# Adafruit_PN532_Breakout_v1_6.net
KiCad netlist of a schematic drawn in EAGLE
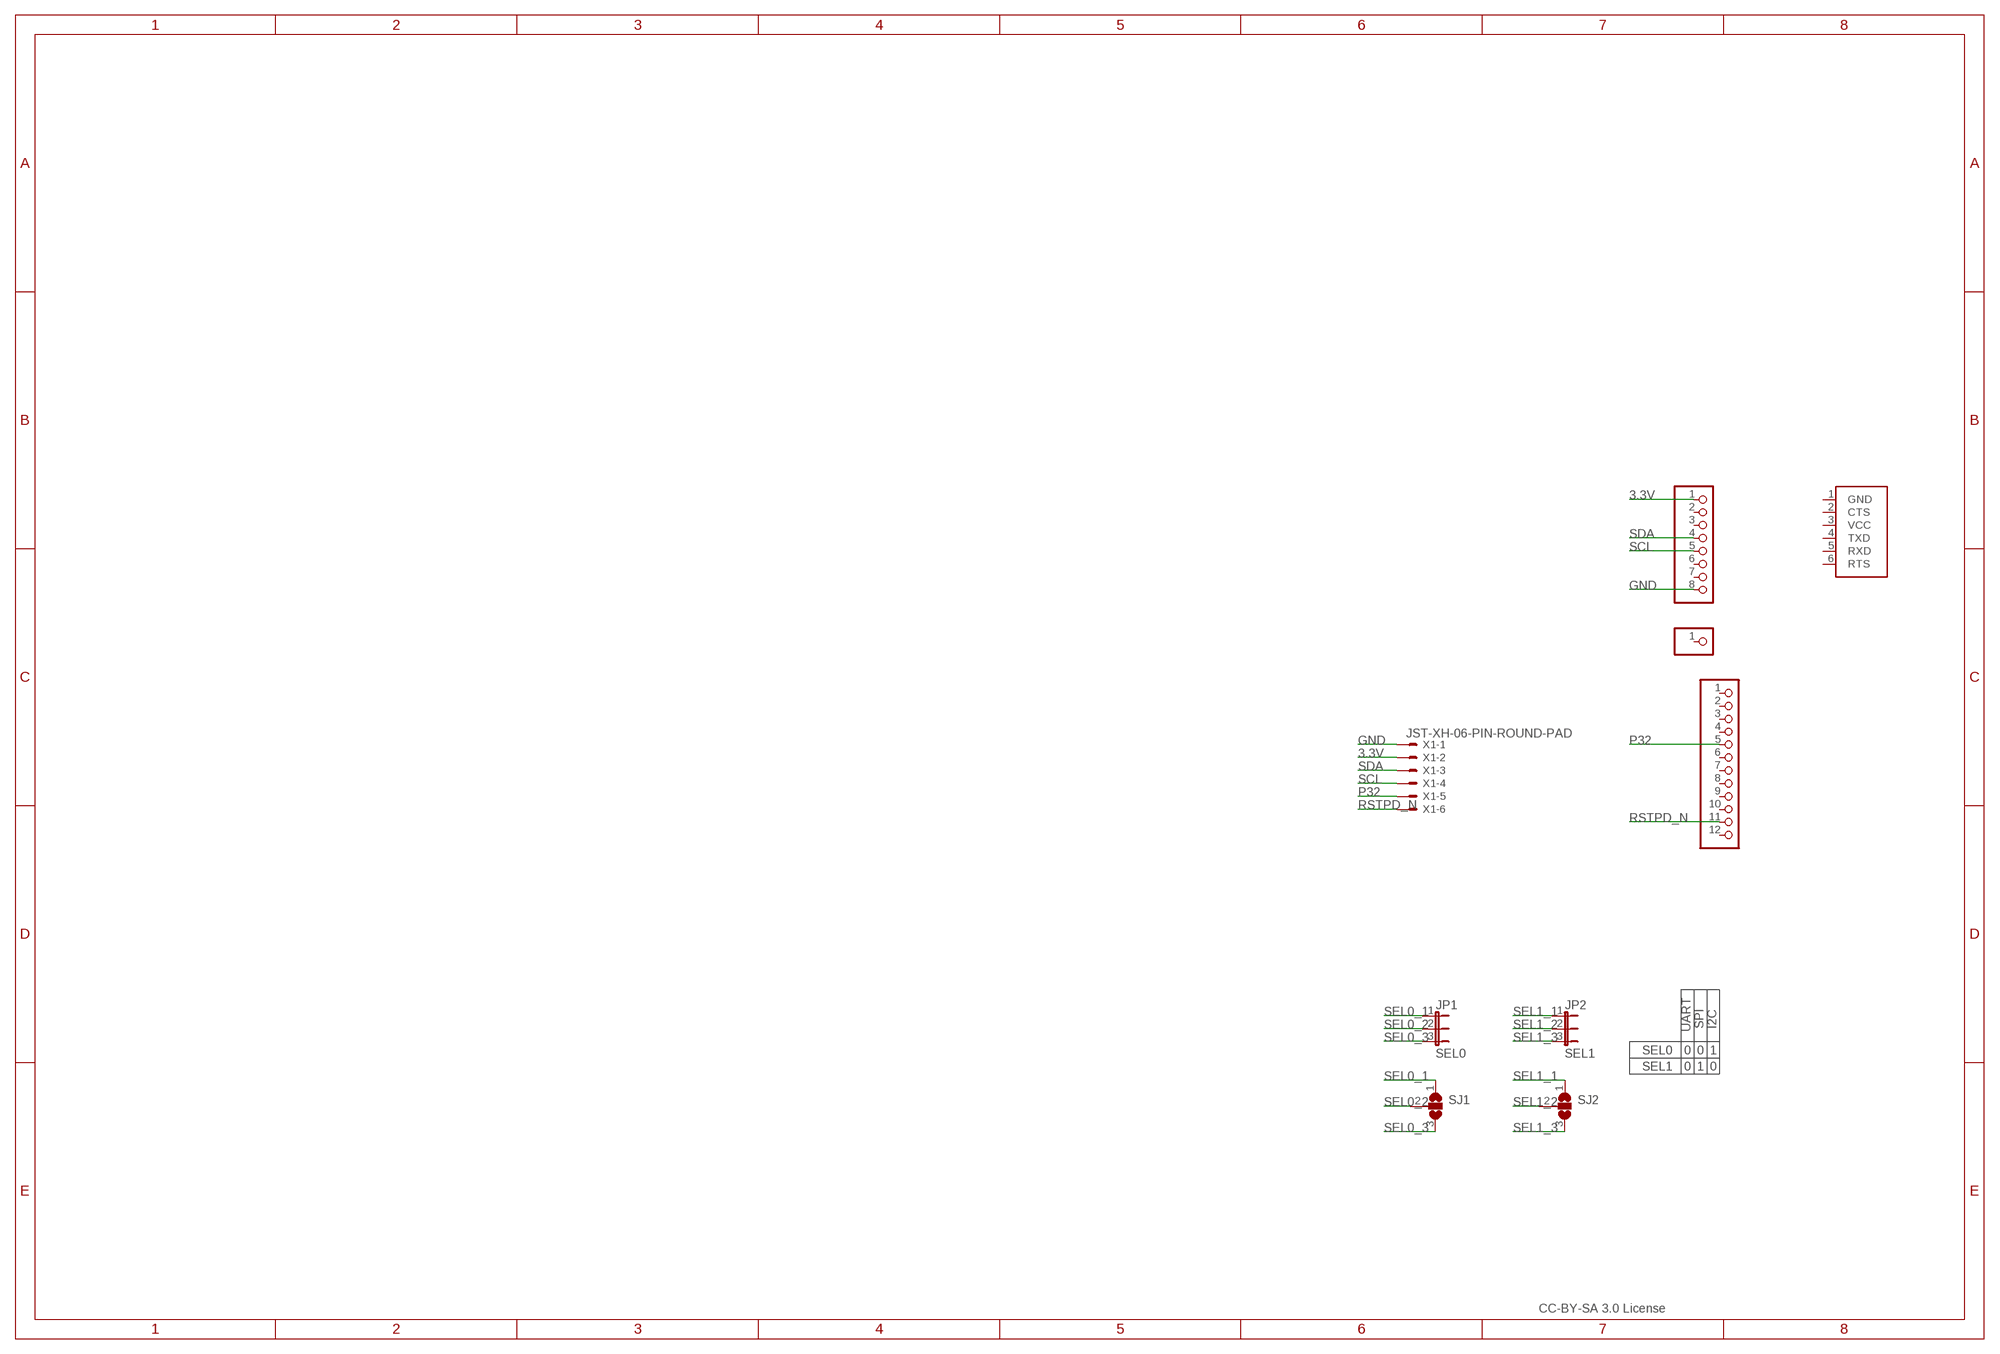
[diagram p0: schematic, sheet 1]

(export (version "E")
  (design (tool "Eeschema 10.0.6"))
  (components
    (comp (ref "CN1")
      (value "FTDI")
      (footprint "eagle-import:1X06_ROUND")
      (libsource (lib "eagle-import") (part "FTDIUSBCABLE"))
    )
    (comp (ref "JP1")
      (value "SEL0")
      (footprint "eagle-import:JUMPER3")
      (libsource (lib "eagle-import") (part "JUMPER3"))
    )
    (comp (ref "JP2")
      (value "SEL1")
      (footprint "eagle-import:JUMPER3")
      (libsource (lib "eagle-import") (part "JUMPER3"))
    )
    (comp (ref "JP3")
      (value "HEADER-1X12")
      (footprint "eagle-import:1X12_ROUND")
      (libsource (lib "eagle-import") (part "HEADER-1X12"))
    )
    (comp (ref "JP4")
      (value "HEADER-1X8ROUND")
      (footprint "eagle-import:1X08_ROUND")
      (libsource (lib "eagle-import") (part "HEADER-1X8ROUND"))
    )
    (comp (ref "JP5")
      (value "HEADER-1X1ROUND")
      (footprint "eagle-import:1X01_ROUND")
      (libsource (lib "eagle-import") (part "HEADER-1X1ROUND"))
    )
    (comp (ref "SJ1")
      (value "SJ2W")
      (footprint "eagle-import:SJ_2")
      (libsource (lib "eagle-import") (part "SJ2W"))
    )
    (comp (ref "SJ2")
      (value "SJ2W")
      (footprint "eagle-import:SJ_2")
      (libsource (lib "eagle-import") (part "SJ2W"))
    )
    (comp (ref "X1")
      (value "JST-XH-06-PIN-ROUND-PAD")
      (footprint "eagle-import:JST-XH-06-PACKAGE-ROUND-PAD")
      (libsource (lib "eagle-import") (part "JST-XH-06-PIN-ROUND-PAD"))
    )
  )
  (nets
    (net (code "1") (name "/3.3V") (class "Default")
      (node (ref "JP4") (pin "1") (pinfunction "1_1") (pintype "passive"))
      (node (ref "X1") (pin "2") (pinfunction "S_2") (pintype "passive"))
    )
    (net (code "2") (name "/GND") (class "Default")
      (node (ref "JP4") (pin "8") (pinfunction "8_8") (pintype "passive"))
      (node (ref "X1") (pin "1") (pinfunction "S_1") (pintype "passive"))
    )
    (net (code "3") (name "/P32") (class "Default")
      (node (ref "JP3") (pin "5") (pinfunction "5_5") (pintype "passive"))
      (node (ref "X1") (pin "5") (pinfunction "S_5") (pintype "passive"))
    )
    (net (code "4") (name "/RSTPD_N") (class "Default")
      (node (ref "JP3") (pin "11") (pinfunction "11_11") (pintype "passive"))
      (node (ref "X1") (pin "6") (pinfunction "S_6") (pintype "passive"))
    )
    (net (code "5") (name "/SCL") (class "Default")
      (node (ref "JP4") (pin "5") (pinfunction "5_5") (pintype "passive"))
      (node (ref "X1") (pin "4") (pinfunction "S_4") (pintype "passive"))
    )
    (net (code "6") (name "/SDA") (class "Default")
      (node (ref "JP4") (pin "4") (pinfunction "4_4") (pintype "passive"))
      (node (ref "X1") (pin "3") (pinfunction "S_3") (pintype "passive"))
    )
    (net (code "7") (name "/SEL0_1") (class "Default")
      (node (ref "JP1") (pin "1") (pinfunction "1_1") (pintype "passive"))
      (node (ref "SJ1") (pin "1") (pinfunction "1_1") (pintype "passive"))
    )
    (net (code "8") (name "/SEL0_2") (class "Default")
      (node (ref "JP1") (pin "2") (pinfunction "2_2") (pintype "passive"))
      (node (ref "SJ1") (pin "2") (pinfunction "2_2") (pintype "passive"))
    )
    (net (code "9") (name "/SEL0_3") (class "Default")
      (node (ref "JP1") (pin "3") (pinfunction "3_3") (pintype "passive"))
      (node (ref "SJ1") (pin "3") (pinfunction "3_3") (pintype "passive"))
    )
    (net (code "10") (name "/SEL1_1") (class "Default")
      (node (ref "JP2") (pin "1") (pinfunction "1_1") (pintype "passive"))
      (node (ref "SJ2") (pin "1") (pinfunction "1_1") (pintype "passive"))
    )
    (net (code "11") (name "/SEL1_2") (class "Default")
      (node (ref "JP2") (pin "2") (pinfunction "2_2") (pintype "passive"))
      (node (ref "SJ2") (pin "2") (pinfunction "2_2") (pintype "passive"))
    )
    (net (code "12") (name "/SEL1_3") (class "Default")
      (node (ref "JP2") (pin "3") (pinfunction "3_3") (pintype "passive"))
      (node (ref "SJ2") (pin "3") (pinfunction "3_3") (pintype "passive"))
    )
    (net (code "13") (name "unconnected-(CN1-CTS-Pad2)") (class "Default")
      (node (ref "CN1") (pin "2") (pinfunction "CTS_2") (pintype "bidirectional"))
    )
    (net (code "14") (name "unconnected-(CN1-GND-Pad1)") (class "Default")
      (node (ref "CN1") (pin "1") (pinfunction "GND_1") (pintype "bidirectional"))
    )
    (net (code "15") (name "unconnected-(CN1-RTS-Pad6)") (class "Default")
      (node (ref "CN1") (pin "6") (pinfunction "RTS_6") (pintype "bidirectional"))
    )
    (net (code "16") (name "unconnected-(CN1-RXD-Pad5)") (class "Default")
      (node (ref "CN1") (pin "5") (pinfunction "RXD_5") (pintype "bidirectional"))
    )
    (net (code "17") (name "unconnected-(CN1-TXD-Pad4)") (class "Default")
      (node (ref "CN1") (pin "4") (pinfunction "TXD_4") (pintype "bidirectional"))
    )
    (net (code "18") (name "unconnected-(CN1-VCC-Pad3)") (class "Default")
      (node (ref "CN1") (pin "3") (pinfunction "VCC_3") (pintype "bidirectional"))
    )
    (net (code "19") (name "unconnected-(JP3-Pad1)") (class "Default")
      (node (ref "JP3") (pin "1") (pinfunction "1_1") (pintype "passive"))
    )
    (net (code "20") (name "unconnected-(JP3-Pad2)") (class "Default")
      (node (ref "JP3") (pin "2") (pinfunction "2_2") (pintype "passive"))
    )
    (net (code "21") (name "unconnected-(JP3-Pad3)") (class "Default")
      (node (ref "JP3") (pin "3") (pinfunction "3_3") (pintype "passive"))
    )
    (net (code "22") (name "unconnected-(JP3-Pad4)") (class "Default")
      (node (ref "JP3") (pin "4") (pinfunction "4_4") (pintype "passive"))
    )
    (net (code "23") (name "unconnected-(JP3-Pad6)") (class "Default")
      (node (ref "JP3") (pin "6") (pinfunction "6_6") (pintype "passive"))
    )
    (net (code "24") (name "unconnected-(JP3-Pad7)") (class "Default")
      (node (ref "JP3") (pin "7") (pinfunction "7_7") (pintype "passive"))
    )
    (net (code "25") (name "unconnected-(JP3-Pad8)") (class "Default")
      (node (ref "JP3") (pin "8") (pinfunction "8_8") (pintype "passive"))
    )
    (net (code "26") (name "unconnected-(JP3-Pad9)") (class "Default")
      (node (ref "JP3") (pin "9") (pinfunction "9_9") (pintype "passive"))
    )
    (net (code "27") (name "unconnected-(JP3-Pad10)") (class "Default")
      (node (ref "JP3") (pin "10") (pinfunction "10_10") (pintype "passive"))
    )
    (net (code "28") (name "unconnected-(JP3-Pad12)") (class "Default")
      (node (ref "JP3") (pin "12") (pinfunction "12_12") (pintype "passive"))
    )
    (net (code "29") (name "unconnected-(JP4-Pad2)") (class "Default")
      (node (ref "JP4") (pin "2") (pinfunction "2_2") (pintype "passive"))
    )
    (net (code "30") (name "unconnected-(JP4-Pad3)") (class "Default")
      (node (ref "JP4") (pin "3") (pinfunction "3_3") (pintype "passive"))
    )
    (net (code "31") (name "unconnected-(JP4-Pad6)") (class "Default")
      (node (ref "JP4") (pin "6") (pinfunction "6_6") (pintype "passive"))
    )
    (net (code "32") (name "unconnected-(JP4-Pad7)") (class "Default")
      (node (ref "JP4") (pin "7") (pinfunction "7_7") (pintype "passive"))
    )
    (net (code "33") (name "unconnected-(JP5-Pad1)") (class "Default")
      (node (ref "JP5") (pin "1") (pinfunction "1_1") (pintype "passive"))
    )
  )
)
